# SNES_TST_Sheet5.net
KiCad netlist of a schematic drawn in Altium Designer
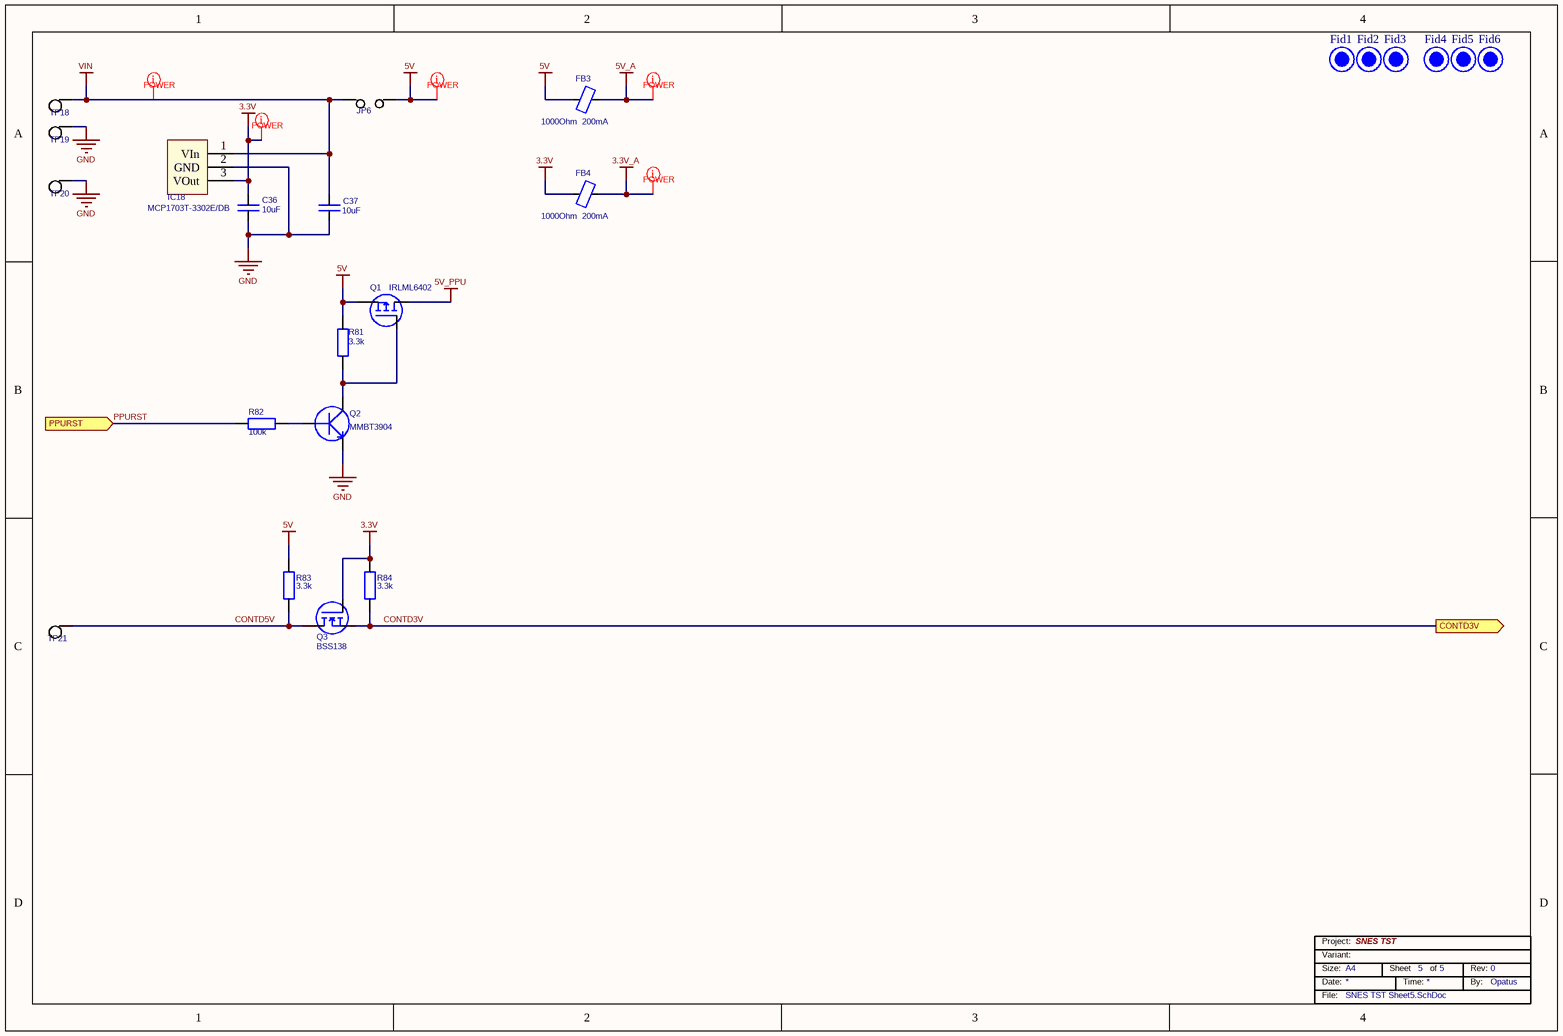
[diagram p0: SNES TST Sheet5.SchDoc]

(export (version "E")
  (design (tool "Eeschema 10.0.6"))
  (components
    (comp (ref "C36")
      (value "10uF")
      (footprint "Cap_0805_Chip")
      (fields
        (field (name "TOLERANCE") "±20%")
        (field (name "Comment") "Ceramic Capacitor 10uF 10V ±20% X7R 0805")
      )
      (libsource (lib "PCB") (part "Capacitor"))
    )
    (comp (ref "C37")
      (value "10uF")
      (footprint "Cap_1206_Chip")
      (fields
        (field (name "TOLERANCE") "±20%")
        (field (name "Comment") "Ceramic Capacitor 10uF 25V ±20% X7R 1206")
      )
      (libsource (lib "PCB") (part "Capacitor"))
    )
    (comp (ref "FB3")
      (value "1000Ohm  200mA")
      (footprint "Ind_0402_Chip")
      (fields (field (name "MANUFACTURER_PART_NUMBER") "MMZ1005S102CT000"))
      (libsource (lib "PCB") (part "Ferrite Bead"))
    )
    (comp (ref "FB4")
      (value "1000Ohm  200mA")
      (footprint "Ind_0402_Chip")
      (fields (field (name "MANUFACTURER_PART_NUMBER") "MMZ1005S102CT000"))
      (libsource (lib "PCB") (part "Ferrite Bead"))
    )
    (comp (ref "Fid1")
      (value "Fiducial")
      (footprint "Fiducial_1_side")
      (libsource (lib "PCB") (part "Fiducial"))
    )
    (comp (ref "Fid2")
      (value "Fiducial")
      (footprint "Fiducial_1_side")
      (libsource (lib "PCB") (part "Fiducial"))
    )
    (comp (ref "Fid3")
      (value "Fiducial")
      (footprint "Fiducial_1_side")
      (libsource (lib "PCB") (part "Fiducial"))
    )
    (comp (ref "Fid4")
      (value "Fiducial")
      (footprint "Fiducial_1_side")
      (libsource (lib "PCB") (part "Fiducial"))
    )
    (comp (ref "Fid5")
      (value "Fiducial")
      (footprint "Fiducial_1_side")
      (libsource (lib "PCB") (part "Fiducial"))
    )
    (comp (ref "Fid6")
      (value "Fiducial")
      (footprint "Fiducial_1_side")
      (libsource (lib "PCB") (part "Fiducial"))
    )
    (comp (ref "IC18")
      (value "MCP1703T")
      (footprint "SOT223-3")
      (description "3.3V Regulator")
      (fields (field (name "MANUFACTURER_PART_NUMBER") "MCP1703T-3302E/DB"))
      (libsource (lib "PCB") (part "MCP1703 SOT223"))
    )
    (comp (ref "JP6") (value "Jumper") (footprint "Jumper Big") (libsource (lib "PCB") (part "Jumper")))
    (comp (ref "Q1") (value "IRLML6402") (footprint "SOT23_FET") (libsource (lib "PCB") (part "Mosfet1")))
    (comp (ref "Q2") (value "MMBT3904") (footprint "SOT23_Transistor") (libsource (lib "PCB") (part "T_NPN")))
    (comp (ref "Q3") (value "BSS138") (footprint "SOT23_FET") (libsource (lib "PCB") (part "Mosfet N")))
    (comp (ref "R81")
      (value "3.3k")
      (footprint "Res_0402_Chip")
      (fields (field (name "TOLERANCE") "±1%") (field (name "Comment") "Resistor 3.3k 0402 ±1%"))
      (libsource (lib "") (part "R_1"))
    )
    (comp (ref "R82")
      (value "100k")
      (footprint "Res_0402_Chip")
      (fields (field (name "TOLERANCE") "±1%") (field (name "Comment") "Resistor 100k 0402 ±1%"))
      (libsource (lib "") (part "R_2"))
    )
    (comp (ref "R83")
      (value "3.3k")
      (footprint "Res_0402_Chip")
      (fields (field (name "TOLERANCE") "±1%") (field (name "Comment") "Resistor 3.3k 0402 ±1%"))
      (libsource (lib "PCB") (part "R"))
    )
    (comp (ref "R84")
      (value "3.3k")
      (footprint "Res_0402_Chip")
      (fields (field (name "TOLERANCE") "±1%") (field (name "Comment") "Resistor 3.3k 0402 ±1%"))
      (libsource (lib "PCB") (part "R"))
    )
    (comp (ref "TP18")
      (value "Pin Connector")
      (footprint "Pin Connector Small")
      (libsource (lib "PCB") (part "Pin Connector"))
    )
    (comp (ref "TP19")
      (value "Pin Connector")
      (footprint "Pin Connector Small")
      (libsource (lib "PCB") (part "Pin Connector"))
    )
    (comp (ref "TP20")
      (value "Pin Connector")
      (footprint "Pin Connector Small")
      (libsource (lib "PCB") (part "Pin Connector"))
    )
    (comp (ref "TP21")
      (value "Pin Connector")
      (footprint "Pin Connector Small")
      (libsource (lib "PCB") (part "Pin Connector"))
    )
  )
  (nets
    (net (code "1") (name "/CONTD3V") (class "Default")
      (node (ref "Q3") (pin "S") (pinfunction "S_S") (pintype "passive"))
      (node (ref "R84") (pin "1") (pintype "passive"))
    )
    (net (code "2") (name "/CONTD5V") (class "Default")
      (node (ref "Q3") (pin "D") (pinfunction "D_D") (pintype "passive"))
      (node (ref "R83") (pin "1") (pintype "passive"))
      (node (ref "TP21") (pin "1") (pinfunction "0_1") (pintype "passive"))
    )
    (net (code "3") (name "/PPURST") (class "Default") (node (ref "R82") (pin "1") (pintype "passive")))
    (net (code "4") (name "3.3V") (class "Default")
      (node (ref "C36") (pin "2") (pintype "passive"))
      (node (ref "FB4") (pin "1") (pintype "passive"))
      (node (ref "IC18") (pin "3") (pinfunction "VOut_3") (pintype "passive"))
      (node (ref "Q3") (pin "G") (pinfunction "G_G") (pintype "passive"))
      (node (ref "R84") (pin "2") (pintype "passive"))
    )
    (net (code "5") (name "3.3V_A") (class "Default") (node (ref "FB4") (pin "2") (pintype "passive")))
    (net (code "6") (name "5V") (class "Default")
      (node (ref "FB3") (pin "1") (pintype "passive"))
      (node (ref "JP6") (pin "1") (pinfunction "0_1") (pintype "passive"))
      (node (ref "Q1") (pin "S") (pinfunction "S_S") (pintype "passive"))
      (node (ref "R81") (pin "1") (pintype "passive"))
      (node (ref "R83") (pin "2") (pintype "passive"))
    )
    (net (code "7") (name "5V_A") (class "Default") (node (ref "FB3") (pin "2") (pintype "passive")))
    (net (code "8") (name "5V_PPU") (class "Default")
      (node (ref "Q1") (pin "D") (pinfunction "D_D") (pintype "passive"))
    )
    (net (code "9") (name "GND") (class "Default")
      (node (ref "C36") (pin "1") (pintype "passive"))
      (node (ref "C37") (pin "1") (pintype "passive"))
      (node (ref "IC18") (pin "2") (pinfunction "GND_2") (pintype "passive"))
      (node (ref "Q2") (pin "E") (pinfunction "E_E") (pintype "passive"))
      (node (ref "TP19") (pin "1") (pinfunction "0_1") (pintype "passive"))
      (node (ref "TP20") (pin "1") (pinfunction "0_1") (pintype "passive"))
    )
    (net (code "10") (name "Net-(Q1-PadG)") (class "Default")
      (node (ref "Q1") (pin "G") (pinfunction "G_G") (pintype "passive"))
      (node (ref "Q2") (pin "C") (pinfunction "C_C") (pintype "passive"))
      (node (ref "R81") (pin "2") (pintype "passive"))
    )
    (net (code "11") (name "Net-(Q2-PadB)") (class "Default")
      (node (ref "Q2") (pin "B") (pinfunction "B_B") (pintype "passive"))
      (node (ref "R82") (pin "2") (pintype "passive"))
    )
    (net (code "12") (name "VIN") (class "Default")
      (node (ref "C37") (pin "2") (pintype "passive"))
      (node (ref "IC18") (pin "1") (pinfunction "VIn_1") (pintype "passive"))
      (node (ref "JP6") (pin "2") (pinfunction "0_2") (pintype "passive"))
      (node (ref "TP18") (pin "1") (pinfunction "0_1") (pintype "passive"))
    )
  )
)
